# RJ45_Ethernet.net
KiCad netlist of a schematic drawn in Altium Designer
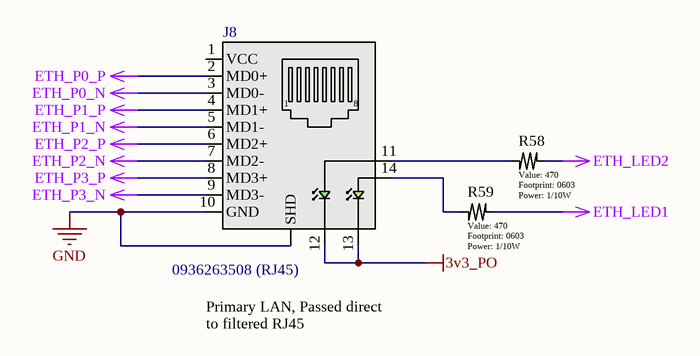
[diagram p0: RJ45_Ethernet.SchDoc]

(export (version "E")
  (design (tool "Eeschema 10.0.6"))
  (components
    (comp (ref "J8")
      (value "0936263508 (RJ45)")
      (footprint "0936263508")
      (description "1 Port RJ45Through Hole 10/100/1000 Base-T, AutoMDIX")
      (libsource (lib "Connectors") (part "0936263508  (RJ45)"))
    )
    (comp (ref "R58")
      (value "470")
      (footprint "0603")
      (fields
        (field (name "TOLERANCE") "1%")
        (field (name "POWER") "1/10W")
        (field (name "Comment") "Generic Resistor")
      )
      (libsource (lib "Resistors") (part "Generic Resistor"))
    )
    (comp (ref "R59")
      (value "470")
      (footprint "0603")
      (fields
        (field (name "TOLERANCE") "1%")
        (field (name "POWER") "1/10W")
        (field (name "Comment") "Generic Resistor")
      )
      (libsource (lib "Resistors") (part "Generic Resistor"))
    )
  )
  (nets
    (net (code "1") (name "3v3_PO") (class "Default")
      (node (ref "J8") (pin "12") (pinfunction "Cathode_12") (pintype "passive"))
      (node (ref "J8") (pin "13") (pinfunction "Cathode_13") (pintype "passive"))
    )
    (net (code "2") (name "ETH_LED1") (class "Default")
      (node (ref "R59") (pin "2") (pinfunction "2_2") (pintype "passive"))
    )
    (net (code "3") (name "ETH_LED2") (class "Default")
      (node (ref "R58") (pin "2") (pinfunction "2_2") (pintype "passive"))
    )
    (net (code "4") (name "ETH_P0_N") (class "Default")
      (node (ref "J8") (pin "3") (pinfunction "MD0-_3") (pintype "passive"))
    )
    (net (code "5") (name "ETH_P0_P") (class "Default")
      (node (ref "J8") (pin "2") (pinfunction "MD0+_2") (pintype "passive"))
    )
    (net (code "6") (name "ETH_P1_N") (class "Default")
      (node (ref "J8") (pin "5") (pinfunction "MD1-_5") (pintype "passive"))
    )
    (net (code "7") (name "ETH_P1_P") (class "Default")
      (node (ref "J8") (pin "4") (pinfunction "MD1+_4") (pintype "passive"))
    )
    (net (code "8") (name "ETH_P2_N") (class "Default")
      (node (ref "J8") (pin "7") (pinfunction "MD2-_7") (pintype "passive"))
    )
    (net (code "9") (name "ETH_P2_P") (class "Default")
      (node (ref "J8") (pin "6") (pinfunction "MD2+_6") (pintype "passive"))
    )
    (net (code "10") (name "ETH_P3_N") (class "Default")
      (node (ref "J8") (pin "9") (pinfunction "MD3-_9") (pintype "passive"))
    )
    (net (code "11") (name "ETH_P3_P") (class "Default")
      (node (ref "J8") (pin "8") (pinfunction "MD3+_8") (pintype "passive"))
    )
    (net (code "12") (name "GND") (class "Default")
      (node (ref "J8") (pin "10") (pinfunction "GND_10") (pintype "passive"))
      (node (ref "J8") (pin "SHD") (pinfunction "SHD_SHD") (pintype "passive"))
    )
    (net (code "13") (name "Net-(J8-Anode-Pad11)") (class "Default")
      (node (ref "J8") (pin "11") (pinfunction "Anode_11") (pintype "passive"))
      (node (ref "R58") (pin "1") (pinfunction "1_1") (pintype "passive"))
    )
    (net (code "14") (name "Net-(J8-Anode-Pad14)") (class "Default")
      (node (ref "J8") (pin "14") (pinfunction "Anode_14") (pintype "passive"))
      (node (ref "R59") (pin "1") (pinfunction "1_1") (pintype "passive"))
    )
    (net (code "15") (name "unconnected-(J8-VCC-Pad1)") (class "Default")
      (node (ref "J8") (pin "1") (pinfunction "VCC_1") (pintype "passive"))
    )
  )
)
